# sandwich.net
KiCad netlist of a schematic drawn in EAGLE
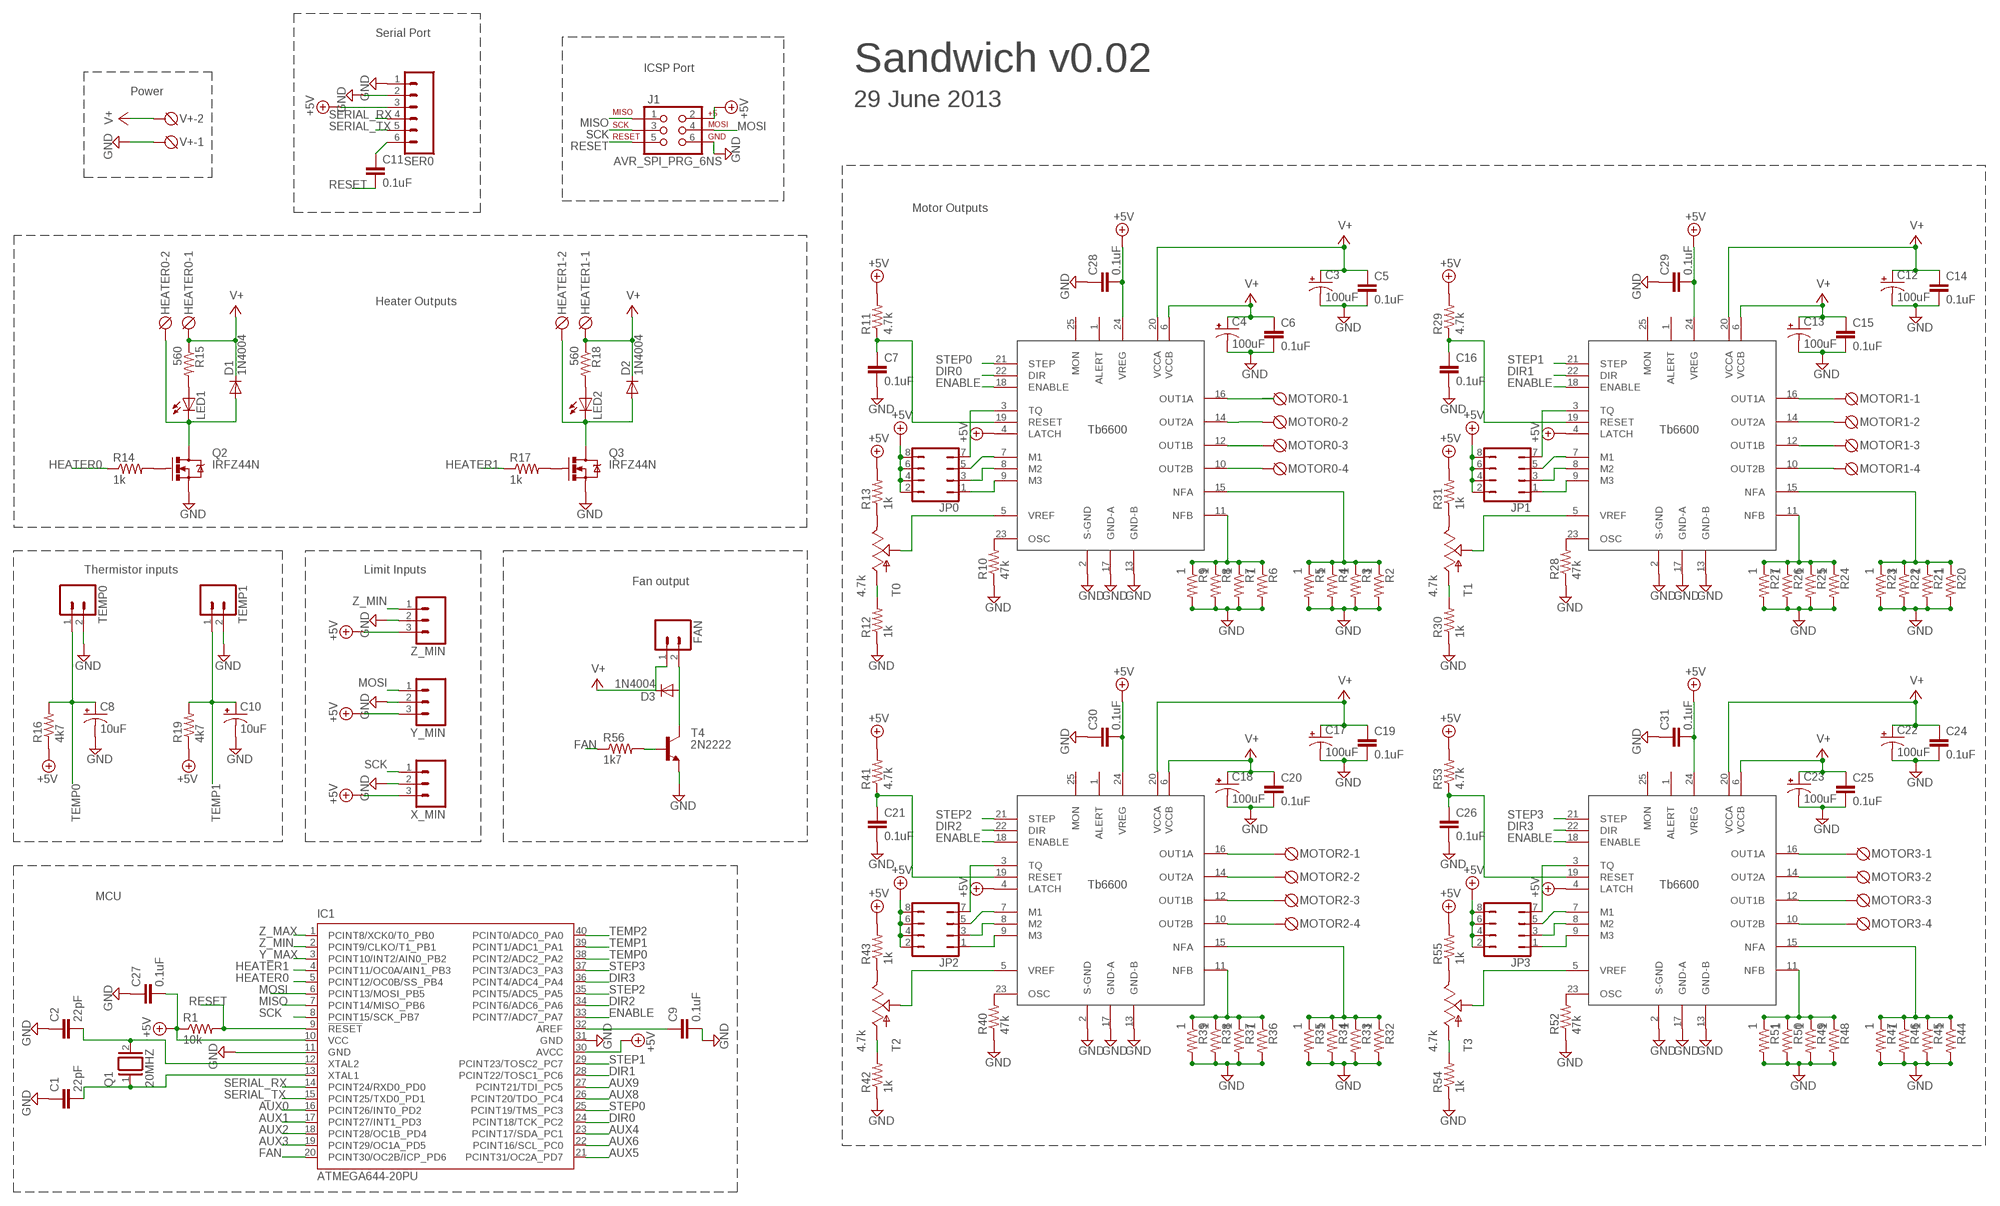
[diagram p0: schematic, sheet 1]

(export (version "E")
  (design (tool "Eeschema 10.0.6"))
  (components
    (comp (ref "C1")
      (value "22pF")
      (footprint "eagle-import:CAP-PTH-SMALL2")
      (libsource (lib "eagle-import") (part "CAPPTH2"))
    )
    (comp (ref "C2")
      (value "22pF")
      (footprint "eagle-import:CAP-PTH-SMALL2")
      (libsource (lib "eagle-import") (part "CAPPTH2"))
    )
    (comp (ref "C3")
      (value "100uF")
      (footprint "eagle-import:CPOL-RADIAL-10UF-25V")
      (libsource (lib "eagle-import") (part "SparkFun-Passives_CAP_POLPTH2"))
    )
    (comp (ref "C4")
      (value "100uF")
      (footprint "eagle-import:CPOL-RADIAL-10UF-25V")
      (libsource (lib "eagle-import") (part "SparkFun-Passives_CAP_POLPTH2"))
    )
    (comp (ref "C5")
      (value "0.1uF")
      (footprint "eagle-import:CAP-PTH-SMALL")
      (libsource (lib "eagle-import") (part "CAPPTH"))
    )
    (comp (ref "C6")
      (value "0.1uF")
      (footprint "eagle-import:CAP-PTH-SMALL")
      (libsource (lib "eagle-import") (part "CAPPTH"))
    )
    (comp (ref "C7")
      (value "0.1uF")
      (footprint "eagle-import:CAP-PTH-SMALL")
      (libsource (lib "eagle-import") (part "CAPPTH"))
    )
    (comp (ref "C8")
      (value "10uF")
      (footprint "eagle-import:CPOL-RADIAL-10UF-25V")
      (libsource (lib "eagle-import") (part "CAP_POLPTH2"))
    )
    (comp (ref "C9")
      (value "0.1uF")
      (footprint "eagle-import:CAP-PTH-SMALL")
      (libsource (lib "eagle-import") (part "CAPPTH"))
    )
    (comp (ref "C10")
      (value "10uF")
      (footprint "eagle-import:CPOL-RADIAL-10UF-25V")
      (libsource (lib "eagle-import") (part "CAP_POLPTH2"))
    )
    (comp (ref "C11")
      (value "0.1uF")
      (footprint "eagle-import:CAP-PTH-SMALL")
      (libsource (lib "eagle-import") (part "SparkFun-Passives_CAPPTH"))
    )
    (comp (ref "C12")
      (value "100uF")
      (footprint "eagle-import:CPOL-RADIAL-10UF-25V")
      (libsource (lib "eagle-import") (part "SparkFun-Passives_CAP_POLPTH2"))
    )
    (comp (ref "C13")
      (value "100uF")
      (footprint "eagle-import:CPOL-RADIAL-10UF-25V")
      (libsource (lib "eagle-import") (part "SparkFun-Passives_CAP_POLPTH2"))
    )
    (comp (ref "C14")
      (value "0.1uF")
      (footprint "eagle-import:CAP-PTH-SMALL")
      (libsource (lib "eagle-import") (part "CAPPTH"))
    )
    (comp (ref "C15")
      (value "0.1uF")
      (footprint "eagle-import:CAP-PTH-SMALL")
      (libsource (lib "eagle-import") (part "CAPPTH"))
    )
    (comp (ref "C16")
      (value "0.1uF")
      (footprint "eagle-import:CAP-PTH-SMALL")
      (libsource (lib "eagle-import") (part "CAPPTH"))
    )
    (comp (ref "C17")
      (value "100uF")
      (footprint "eagle-import:CPOL-RADIAL-10UF-25V")
      (libsource (lib "eagle-import") (part "SparkFun-Passives_CAP_POLPTH2"))
    )
    (comp (ref "C18")
      (value "100uF")
      (footprint "eagle-import:CPOL-RADIAL-10UF-25V")
      (libsource (lib "eagle-import") (part "SparkFun-Passives_CAP_POLPTH2"))
    )
    (comp (ref "C19")
      (value "0.1uF")
      (footprint "eagle-import:CAP-PTH-SMALL")
      (libsource (lib "eagle-import") (part "CAPPTH"))
    )
    (comp (ref "C20")
      (value "0.1uF")
      (footprint "eagle-import:CAP-PTH-SMALL")
      (libsource (lib "eagle-import") (part "CAPPTH"))
    )
    (comp (ref "C21")
      (value "0.1uF")
      (footprint "eagle-import:CAP-PTH-SMALL")
      (libsource (lib "eagle-import") (part "CAPPTH"))
    )
    (comp (ref "C22")
      (value "100uF")
      (footprint "eagle-import:CPOL-RADIAL-10UF-25V")
      (libsource (lib "eagle-import") (part "SparkFun-Passives_CAP_POLPTH2"))
    )
    (comp (ref "C23")
      (value "100uF")
      (footprint "eagle-import:CPOL-RADIAL-10UF-25V")
      (libsource (lib "eagle-import") (part "SparkFun-Passives_CAP_POLPTH2"))
    )
    (comp (ref "C24")
      (value "0.1uF")
      (footprint "eagle-import:CAP-PTH-SMALL")
      (libsource (lib "eagle-import") (part "CAPPTH"))
    )
    (comp (ref "C25")
      (value "0.1uF")
      (footprint "eagle-import:CAP-PTH-SMALL")
      (libsource (lib "eagle-import") (part "CAPPTH"))
    )
    (comp (ref "C26")
      (value "0.1uF")
      (footprint "eagle-import:CAP-PTH-SMALL")
      (libsource (lib "eagle-import") (part "CAPPTH"))
    )
    (comp (ref "C27")
      (value "0.1uF")
      (footprint "eagle-import:CAP-PTH-SMALL")
      (libsource (lib "eagle-import") (part "CAPPTH"))
    )
    (comp (ref "C28")
      (value "0.1uF")
      (footprint "eagle-import:CAP-PTH-SMALL")
      (libsource (lib "eagle-import") (part "CAPPTH"))
    )
    (comp (ref "C29")
      (value "0.1uF")
      (footprint "eagle-import:CAP-PTH-SMALL")
      (libsource (lib "eagle-import") (part "CAPPTH"))
    )
    (comp (ref "C30")
      (value "0.1uF")
      (footprint "eagle-import:CAP-PTH-SMALL")
      (libsource (lib "eagle-import") (part "CAPPTH"))
    )
    (comp (ref "C31")
      (value "0.1uF")
      (footprint "eagle-import:CAP-PTH-SMALL")
      (libsource (lib "eagle-import") (part "CAPPTH"))
    )
    (comp (ref "D1")
      (value "1N4004")
      (footprint "eagle-import:DO41-10")
      (libsource (lib "eagle-import") (part "1N4004"))
    )
    (comp (ref "D2")
      (value "1N4004")
      (footprint "eagle-import:DO41-10")
      (libsource (lib "eagle-import") (part "1N4004"))
    )
    (comp (ref "D3")
      (value "1N4004")
      (footprint "eagle-import:DIODE-1N4001")
      (libsource (lib "eagle-import") (part "DIODEPTH"))
    )
    (comp (ref "FAN")
      (value "M02PTH3")
      (footprint "eagle-import:1X02_LONGPADS")
      (libsource (lib "eagle-import") (part "M02PTH3"))
    )
    (comp (ref "HEATER0")
      (value "DG3XX-02-3.5")
      (footprint "eagle-import:DG350-3.5-02P")
      (libsource (lib "eagle-import") (part "DG3XX-02-3.5"))
    )
    (comp (ref "HEATER1")
      (value "DG3XX-02-3.5")
      (footprint "eagle-import:DG350-3.5-02P")
      (libsource (lib "eagle-import") (part "DG3XX-02-3.5"))
    )
    (comp (ref "IC1")
      (value "ATMEGA644-20PU")
      (footprint "eagle-import:DIL40")
      (libsource (lib "eagle-import") (part "ATMEGA644-PU20"))
    )
    (comp (ref "J1")
      (value "AVR_SPI_PRG_6NS")
      (footprint "eagle-import:2X3-NS")
      (libsource (lib "eagle-import") (part "AVR_SPI_PRG_6NS"))
    )
    (comp (ref "JP0")
      (value "JP4Q")
      (footprint "eagle-import:JP4Q")
      (libsource (lib "eagle-import") (part "JP4Q"))
    )
    (comp (ref "JP1")
      (value "JP4Q")
      (footprint "eagle-import:JP4Q")
      (libsource (lib "eagle-import") (part "JP4Q"))
    )
    (comp (ref "JP2")
      (value "JP4Q")
      (footprint "eagle-import:JP4Q")
      (libsource (lib "eagle-import") (part "JP4Q"))
    )
    (comp (ref "JP3")
      (value "JP4Q")
      (footprint "eagle-import:JP4Q")
      (libsource (lib "eagle-import") (part "JP4Q"))
    )
    (comp (ref "LED1")
      (value "LED5MM")
      (footprint "eagle-import:LED5MM")
      (libsource (lib "eagle-import") (part "LED5MM"))
    )
    (comp (ref "LED2")
      (value "LED5MM")
      (footprint "eagle-import:LED5MM")
      (libsource (lib "eagle-import") (part "LED5MM"))
    )
    (comp (ref "MOTOR0")
      (value "DG3XX-04-3.5")
      (footprint "eagle-import:DG350-3.5-04P")
      (libsource (lib "eagle-import") (part "DG3XX-04-3.5"))
    )
    (comp (ref "MOTOR1")
      (value "DG3XX-04-3.5")
      (footprint "eagle-import:DG350-3.5-04P")
      (libsource (lib "eagle-import") (part "DG3XX-04-3.5"))
    )
    (comp (ref "MOTOR2")
      (value "DG3XX-04-3.5")
      (footprint "eagle-import:DG350-3.5-04P")
      (libsource (lib "eagle-import") (part "DG3XX-04-3.5"))
    )
    (comp (ref "MOTOR3")
      (value "DG3XX-04-3.5")
      (footprint "eagle-import:DG350-3.5-04P")
      (libsource (lib "eagle-import") (part "DG3XX-04-3.5"))
    )
    (comp (ref "Q1")
      (value "20MHZ")
      (footprint "eagle-import:QS")
      (libsource (lib "eagle-import") (part "XTAL/S"))
    )
    (comp (ref "Q2")
      (value "IRFZ44N")
      (footprint "eagle-import:TO220V")
      (libsource (lib "eagle-import") (part "MOSFET-NCHANNELFQP30N06L"))
    )
    (comp (ref "Q3")
      (value "IRFZ44N")
      (footprint "eagle-import:TO220V")
      (libsource (lib "eagle-import") (part "MOSFET-NCHANNELFQP30N06L"))
    )
    (comp (ref "R1")
      (value "10k")
      (footprint "eagle-import:0204V")
      (libsource (lib "eagle-import") (part "R-US_0204/2V"))
    )
    (comp (ref "R2")
      (value "1")
      (footprint "eagle-import:0204V")
      (libsource (lib "eagle-import") (part "R-US_0204/2V"))
    )
    (comp (ref "R3")
      (value "1")
      (footprint "eagle-import:0204V")
      (libsource (lib "eagle-import") (part "R-US_0204/2V"))
    )
    (comp (ref "R4")
      (value "1")
      (footprint "eagle-import:0204V")
      (libsource (lib "eagle-import") (part "R-US_0204/2V"))
    )
    (comp (ref "R5")
      (value "1")
      (footprint "eagle-import:0204V")
      (libsource (lib "eagle-import") (part "R-US_0204/2V"))
    )
    (comp (ref "R6")
      (value "1")
      (footprint "eagle-import:0204V")
      (libsource (lib "eagle-import") (part "R-US_0204/2V"))
    )
    (comp (ref "R7")
      (value "1")
      (footprint "eagle-import:0204V")
      (libsource (lib "eagle-import") (part "R-US_0204/2V"))
    )
    (comp (ref "R8")
      (value "1")
      (footprint "eagle-import:0204V")
      (libsource (lib "eagle-import") (part "R-US_0204/2V"))
    )
    (comp (ref "R9")
      (value "1")
      (footprint "eagle-import:0204V")
      (libsource (lib "eagle-import") (part "R-US_0204/2V"))
    )
    (comp (ref "R10")
      (value "47k")
      (footprint "eagle-import:0204V")
      (libsource (lib "eagle-import") (part "R-US_0204/2V"))
    )
    (comp (ref "R11")
      (value "4.7k")
      (footprint "eagle-import:0204V")
      (libsource (lib "eagle-import") (part "R-US_0204/2V"))
    )
    (comp (ref "R12")
      (value "1k")
      (footprint "eagle-import:0204V")
      (libsource (lib "eagle-import") (part "R-US_0204/2V"))
    )
    (comp (ref "R13")
      (value "1k")
      (footprint "eagle-import:0204V")
      (libsource (lib "eagle-import") (part "R-US_0204/2V"))
    )
    (comp (ref "R14")
      (value "1k")
      (footprint "eagle-import:0204V")
      (libsource (lib "eagle-import") (part "R-US_0204/2V"))
    )
    (comp (ref "R15")
      (value "560")
      (footprint "eagle-import:0204V")
      (libsource (lib "eagle-import") (part "R-US_0204/2V"))
    )
    (comp (ref "R16")
      (value "4k7")
      (footprint "eagle-import:0204V")
      (libsource (lib "eagle-import") (part "R-US_0204/2V"))
    )
    (comp (ref "R17")
      (value "1k")
      (footprint "eagle-import:0204V")
      (libsource (lib "eagle-import") (part "R-US_0204/2V"))
    )
    (comp (ref "R18")
      (value "560")
      (footprint "eagle-import:0204V")
      (libsource (lib "eagle-import") (part "R-US_0204/2V"))
    )
    (comp (ref "R19")
      (value "4k7")
      (footprint "eagle-import:0204V")
      (libsource (lib "eagle-import") (part "R-US_0204/2V"))
    )
    (comp (ref "R20")
      (value "1")
      (footprint "eagle-import:0204V")
      (libsource (lib "eagle-import") (part "R-US_0204/2V"))
    )
    (comp (ref "R21")
      (value "1")
      (footprint "eagle-import:0204V")
      (libsource (lib "eagle-import") (part "R-US_0204/2V"))
    )
    (comp (ref "R22")
      (value "1")
      (footprint "eagle-import:0204V")
      (libsource (lib "eagle-import") (part "R-US_0204/2V"))
    )
    (comp (ref "R23")
      (value "1")
      (footprint "eagle-import:0204V")
      (libsource (lib "eagle-import") (part "R-US_0204/2V"))
    )
    (comp (ref "R24")
      (value "1")
      (footprint "eagle-import:0204V")
      (libsource (lib "eagle-import") (part "R-US_0204/2V"))
    )
    (comp (ref "R25")
      (value "1")
      (footprint "eagle-import:0204V")
      (libsource (lib "eagle-import") (part "R-US_0204/2V"))
    )
    (comp (ref "R26")
      (value "1")
      (footprint "eagle-import:0204V")
      (libsource (lib "eagle-import") (part "R-US_0204/2V"))
    )
    (comp (ref "R27")
      (value "1")
      (footprint "eagle-import:0204V")
      (libsource (lib "eagle-import") (part "R-US_0204/2V"))
    )
    (comp (ref "R28")
      (value "47k")
      (footprint "eagle-import:0204V")
      (libsource (lib "eagle-import") (part "R-US_0204/2V"))
    )
    (comp (ref "R29")
      (value "4.7k")
      (footprint "eagle-import:0204V")
      (libsource (lib "eagle-import") (part "R-US_0204/2V"))
    )
    (comp (ref "R30")
      (value "1k")
      (footprint "eagle-import:0204V")
      (libsource (lib "eagle-import") (part "R-US_0204/2V"))
    )
    (comp (ref "R31")
      (value "1k")
      (footprint "eagle-import:0204V")
      (libsource (lib "eagle-import") (part "R-US_0204/2V"))
    )
    (comp (ref "R32")
      (value "1")
      (footprint "eagle-import:0204V")
      (libsource (lib "eagle-import") (part "R-US_0204/2V"))
    )
    (comp (ref "R33")
      (value "1")
      (footprint "eagle-import:0204V")
      (libsource (lib "eagle-import") (part "R-US_0204/2V"))
    )
    (comp (ref "R34")
      (value "1")
      (footprint "eagle-import:0204V")
      (libsource (lib "eagle-import") (part "R-US_0204/2V"))
    )
    (comp (ref "R35")
      (value "1")
      (footprint "eagle-import:0204V")
      (libsource (lib "eagle-import") (part "R-US_0204/2V"))
    )
    (comp (ref "R36")
      (value "1")
      (footprint "eagle-import:0204V")
      (libsource (lib "eagle-import") (part "R-US_0204/2V"))
    )
    (comp (ref "R37")
      (value "1")
      (footprint "eagle-import:0204V")
      (libsource (lib "eagle-import") (part "R-US_0204/2V"))
    )
    (comp (ref "R38")
      (value "1")
      (footprint "eagle-import:0204V")
      (libsource (lib "eagle-import") (part "R-US_0204/2V"))
    )
    (comp (ref "R39")
      (value "1")
      (footprint "eagle-import:0204V")
      (libsource (lib "eagle-import") (part "R-US_0204/2V"))
    )
    (comp (ref "R40")
      (value "47k")
      (footprint "eagle-import:0204V")
      (libsource (lib "eagle-import") (part "R-US_0204/2V"))
    )
    (comp (ref "R41")
      (value "4.7k")
      (footprint "eagle-import:0204V")
      (libsource (lib "eagle-import") (part "R-US_0204/2V"))
    )
    (comp (ref "R42")
      (value "1k")
      (footprint "eagle-import:0204V")
      (libsource (lib "eagle-import") (part "R-US_0204/2V"))
    )
    (comp (ref "R43")
      (value "1k")
      (footprint "eagle-import:0204V")
      (libsource (lib "eagle-import") (part "R-US_0204/2V"))
    )
    (comp (ref "R44")
      (value "1")
      (footprint "eagle-import:0204V")
      (libsource (lib "eagle-import") (part "R-US_0204/2V"))
    )
    (comp (ref "R45")
      (value "1")
      (footprint "eagle-import:0204V")
      (libsource (lib "eagle-import") (part "R-US_0204/2V"))
    )
    (comp (ref "R46")
      (value "1")
      (footprint "eagle-import:0204V")
      (libsource (lib "eagle-import") (part "R-US_0204/2V"))
    )
    (comp (ref "R47")
      (value "1")
      (footprint "eagle-import:0204V")
      (libsource (lib "eagle-import") (part "R-US_0204/2V"))
    )
    (comp (ref "R48")
      (value "1")
      (footprint "eagle-import:0204V")
      (libsource (lib "eagle-import") (part "R-US_0204/2V"))
    )
    (comp (ref "R49")
      (value "1")
      (footprint "eagle-import:0204V")
      (libsource (lib "eagle-import") (part "R-US_0204/2V"))
    )
    (comp (ref "R50")
      (value "1")
      (footprint "eagle-import:0204V")
      (libsource (lib "eagle-import") (part "R-US_0204/2V"))
    )
    (comp (ref "R51")
      (value "1")
      (footprint "eagle-import:0204V")
      (libsource (lib "eagle-import") (part "R-US_0204/2V"))
    )
    (comp (ref "R52")
      (value "47k")
      (footprint "eagle-import:0204V")
      (libsource (lib "eagle-import") (part "R-US_0204/2V"))
    )
    (comp (ref "R53")
      (value "4.7k")
      (footprint "eagle-import:0204V")
      (libsource (lib "eagle-import") (part "R-US_0204/2V"))
    )
    (comp (ref "R54")
      (value "1k")
      (footprint "eagle-import:0204V")
      (libsource (lib "eagle-import") (part "R-US_0204/2V"))
    )
    (comp (ref "R55")
      (value "1k")
      (footprint "eagle-import:0204V")
      (libsource (lib "eagle-import") (part "R-US_0204/2V"))
    )
    (comp (ref "R56")
      (value "1k7")
      (footprint "eagle-import:0204V")
      (libsource (lib "eagle-import") (part "R-US_0204/2V"))
    )
    (comp (ref "SER0")
      (value "M06SIP")
      (footprint "eagle-import:1X06")
      (libsource (lib "eagle-import") (part "M06SIP"))
    )
    (comp (ref "T0")
      (value "4.7k")
      (footprint "eagle-import:TRIM_POT")
      (libsource (lib "eagle-import") (part "POTTRIM"))
    )
    (comp (ref "T1")
      (value "4.7k")
      (footprint "eagle-import:TRIM_POT")
      (libsource (lib "eagle-import") (part "POTTRIM"))
    )
    (comp (ref "T2")
      (value "4.7k")
      (footprint "eagle-import:TRIM_POT")
      (libsource (lib "eagle-import") (part "POTTRIM"))
    )
    (comp (ref "T3")
      (value "4.7k")
      (footprint "eagle-import:TRIM_POT")
      (libsource (lib "eagle-import") (part "POTTRIM"))
    )
    (comp (ref "T4")
      (value "2N2222")
      (footprint "eagle-import:TO18")
      (libsource (lib "eagle-import") (part "2N2222"))
    )
    (comp (ref "TEMP0")
      (value "M02PTH3")
      (footprint "eagle-import:1X02_LONGPADS")
      (libsource (lib "eagle-import") (part "M02PTH3"))
    )
    (comp (ref "TEMP1")
      (value "M02PTH3")
      (footprint "eagle-import:1X02_LONGPADS")
      (libsource (lib "eagle-import") (part "M02PTH3"))
    )
    (comp (ref "U$1")
      (value "TB6600HG")
      (footprint "eagle-import:P-HZIP25-1.00G")
      (libsource (lib "eagle-import") (part "TB6600HG"))
    )
    (comp (ref "U$2")
      (value "TB6600HG")
      (footprint "eagle-import:P-HZIP25-1.00G")
      (libsource (lib "eagle-import") (part "TB6600HG"))
    )
    (comp (ref "U$3")
      (value "TB6600HG")
      (footprint "eagle-import:P-HZIP25-1.00G")
      (libsource (lib "eagle-import") (part "TB6600HG"))
    )
    (comp (ref "U$4")
      (value "TB6600HG")
      (footprint "eagle-import:P-HZIP25-1.00G")
      (libsource (lib "eagle-import") (part "TB6600HG"))
    )
    (comp (ref "V+")
      (value "DG3XX-02-3.5")
      (footprint "eagle-import:DG350-3.5-02P")
      (libsource (lib "eagle-import") (part "DG3XX-02-3.5"))
    )
    (comp (ref "X_MIN")
      (value "M03LONGPADS")
      (footprint "eagle-import:1X03_LONGPADS")
      (libsource (lib "eagle-import") (part "M03LONGPADS"))
    )
    (comp (ref "Y_MIN")
      (value "M03LONGPADS")
      (footprint "eagle-import:1X03_LONGPADS")
      (libsource (lib "eagle-import") (part "M03LONGPADS"))
    )
    (comp (ref "Z_MIN")
      (value "M03LONGPADS")
      (footprint "eagle-import:1X03_LONGPADS")
      (libsource (lib "eagle-import") (part "M03LONGPADS"))
    )
  )
  (nets
    (net (code "1") (name "+5V") (class "Default")
      (node (ref "C27") (pin "2") (pinfunction "2_2") (pintype "passive"))
      (node (ref "C28") (pin "2") (pinfunction "2_2") (pintype "passive"))
      (node (ref "C29") (pin "2") (pinfunction "2_2") (pintype "passive"))
      (node (ref "C30") (pin "2") (pinfunction "2_2") (pintype "passive"))
      (node (ref "C31") (pin "2") (pinfunction "2_2") (pintype "passive"))
      (node (ref "IC1") (pin "10") (pinfunction "VCC_10") (pintype "power_in"))
      (node (ref "IC1") (pin "30") (pinfunction "AVCC_30") (pintype "power_in"))
      (node (ref "J1") (pin "2") (pinfunction "2_2") (pintype "passive"))
      (node (ref "JP0") (pin "2") (pinfunction "2_2") (pintype "passive"))
      (node (ref "JP0") (pin "4") (pinfunction "4_4") (pintype "passive"))
      (node (ref "JP0") (pin "6") (pinfunction "6_6") (pintype "passive"))
      (node (ref "JP0") (pin "8") (pinfunction "8_8") (pintype "passive"))
      (node (ref "JP1") (pin "2") (pinfunction "2_2") (pintype "passive"))
      (node (ref "JP1") (pin "4") (pinfunction "4_4") (pintype "passive"))
      (node (ref "JP1") (pin "6") (pinfunction "6_6") (pintype "passive"))
      (node (ref "JP1") (pin "8") (pinfunction "8_8") (pintype "passive"))
      (node (ref "JP2") (pin "2") (pinfunction "2_2") (pintype "passive"))
      (node (ref "JP2") (pin "4") (pinfunction "4_4") (pintype "passive"))
      (node (ref "JP2") (pin "6") (pinfunction "6_6") (pintype "passive"))
      (node (ref "JP2") (pin "8") (pinfunction "8_8") (pintype "passive"))
      (node (ref "JP3") (pin "2") (pinfunction "2_2") (pintype "passive"))
      (node (ref "JP3") (pin "4") (pinfunction "4_4") (pintype "passive"))
      (node (ref "JP3") (pin "6") (pinfunction "6_6") (pintype "passive"))
      (node (ref "JP3") (pin "8") (pinfunction "8_8") (pintype "passive"))
      (node (ref "R1") (pin "1") (pinfunction "1_1") (pintype "passive"))
      (node (ref "R11") (pin "2") (pinfunction "2_2") (pintype "passive"))
      (node (ref "R13") (pin "2") (pinfunction "2_2") (pintype "passive"))
      (node (ref "R16") (pin "1") (pinfunction "1_1") (pintype "passive"))
      (node (ref "R19") (pin "1") (pinfunction "1_1") (pintype "passive"))
      (node (ref "R29") (pin "2") (pinfunction "2_2") (pintype "passive"))
      (node (ref "R31") (pin "2") (pinfunction "2_2") (pintype "passive"))
      (node (ref "R41") (pin "2") (pinfunction "2_2") (pintype "passive"))
      (node (ref "R43") (pin "2") (pinfunction "2_2") (pintype "passive"))
      (node (ref "R53") (pin "2") (pinfunction "2_2") (pintype "passive"))
      (node (ref "R55") (pin "2") (pinfunction "2_2") (pintype "passive"))
      (node (ref "SER0") (pin "3") (pinfunction "3_3") (pintype "passive"))
      (node (ref "U$1") (pin "24") (pinfunction "VREG_24") (pintype "output"))
      (node (ref "U$1") (pin "4") (pinfunction "LATCH_4") (pintype "input"))
      (node (ref "U$2") (pin "24") (pinfunction "VREG_24") (pintype "output"))
      (node (ref "U$2") (pin "4") (pinfunction "LATCH_4") (pintype "input"))
      (node (ref "U$3") (pin "24") (pinfunction "VREG_24") (pintype "output"))
      (node (ref "U$3") (pin "4") (pinfunction "LATCH_4") (pintype "input"))
      (node (ref "U$4") (pin "24") (pinfunction "VREG_24") (pintype "output"))
      (node (ref "U$4") (pin "4") (pinfunction "LATCH_4") (pintype "input"))
      (node (ref "X_MIN") (pin "3") (pinfunction "3_3") (pintype "passive"))
      (node (ref "Y_MIN") (pin "3") (pinfunction "3_3") (pintype "passive"))
      (node (ref "Z_MIN") (pin "3") (pinfunction "3_3") (pintype "passive"))
    )
    (net (code "2") (name "/AUX0") (class "Default")
      (node (ref "IC1") (pin "16") (pinfunction "PCINT26/INT0_PD2_16") (pintype "bidirectional"))
    )
    (net (code "3") (name "/AUX1") (class "Default")
      (node (ref "IC1") (pin "17") (pinfunction "PCINT27/INT1_PD3_17") (pintype "bidirectional"))
    )
    (net (code "4") (name "/AUX2") (class "Default")
      (node (ref "IC1") (pin "18") (pinfunction "PCINT28/OC1B_PD4_18") (pintype "bidirectional"))
    )
    (net (code "5") (name "/AUX3") (class "Default")
      (node (ref "IC1") (pin "19") (pinfunction "PCINT29/OC1A_PD5_19") (pintype "bidirectional"))
    )
    (net (code "6") (name "/AUX4") (class "Default")
      (node (ref "IC1") (pin "23") (pinfunction "PCINT17/SDA_PC1_23") (pintype "bidirectional"))
    )
    (net (code "7") (name "/AUX5") (class "Default")
      (node (ref "IC1") (pin "21") (pinfunction "PCINT31/OC2A_PD7_21") (pintype "bidirectional"))
    )
    (net (code "8") (name "/AUX6") (class "Default")
      (node (ref "IC1") (pin "22") (pinfunction "PCINT16/SCL_PC0_22") (pintype "bidirectional"))
    )
    (net (code "9") (name "/AUX8") (class "Default")
      (node (ref "IC1") (pin "26") (pinfunction "PCINT20/TDO_PC4_26") (pintype "bidirectional"))
    )
    (net (code "10") (name "/AUX9") (class "Default")
      (node (ref "IC1") (pin "27") (pinfunction "PCINT21/TDI_PC5_27") (pintype "bidirectional"))
    )
    (net (code "11") (name "/DIR0") (class "Default")
      (node (ref "IC1") (pin "24") (pinfunction "PCINT18/TCK_PC2_24") (pintype "bidirectional"))
      (node (ref "U$1") (pin "22") (pinfunction "DIR_22") (pintype "input"))
    )
    (net (code "12") (name "/DIR1") (class "Default")
      (node (ref "IC1") (pin "28") (pinfunction "PCINT22/TOSC1_PC6_28") (pintype "bidirectional"))
      (node (ref "U$2") (pin "22") (pinfunction "DIR_22") (pintype "input"))
    )
    (net (code "13") (name "/DIR2") (class "Default")
      (node (ref "IC1") (pin "34") (pinfunction "PCINT6/ADC6_PA6_34") (pintype "bidirectional"))
      (node (ref "U$3") (pin "22") (pinfunction "DIR_22") (pintype "input"))
    )
    (net (code "14") (name "/DIR3") (class "Default")
      (node (ref "IC1") (pin "36") (pinfunction "PCINT4/ADC4_PA4_36") (pintype "bidirectional"))
      (node (ref "U$4") (pin "22") (pinfunction "DIR_22") (pintype "input"))
    )
    (net (code "15") (name "/ENABLE") (class "Default")
      (node (ref "IC1") (pin "33") (pinfunction "PCINT7/ADC7_PA7_33") (pintype "bidirectional"))
      (node (ref "U$1") (pin "18") (pinfunction "ENABLE_18") (pintype "input"))
      (node (ref "U$2") (pin "18") (pinfunction "ENABLE_18") (pintype "input"))
      (node (ref "U$3") (pin "18") (pinfunction "ENABLE_18") (pintype "input"))
      (node (ref "U$4") (pin "18") (pinfunction "ENABLE_18") (pintype "input"))
    )
    (net (code "16") (name "/FAN") (class "Default")
      (node (ref "IC1") (pin "20") (pinfunction "PCINT30/OC2B/ICP_PD6_20") (pintype "bidirectional"))
      (node (ref "R56") (pin "1") (pinfunction "1_1") (pintype "passive"))
    )
    (net (code "17") (name "/HEATER0") (class "Default")
      (node (ref "IC1") (pin "5") (pinfunction "PCINT12/OC0B/SS_PB4_5") (pintype "bidirectional"))
      (node (ref "R14") (pin "1") (pinfunction "1_1") (pintype "passive"))
    )
    (net (code "18") (name "/HEATER1") (class "Default")
      (node (ref "IC1") (pin "4") (pinfunction "PCINT11/OC0A/AIN1_PB3_4") (pintype "bidirectional"))
      (node (ref "R17") (pin "1") (pinfunction "1_1") (pintype "passive"))
    )
    (net (code "19") (name "/MISO") (class "Default")
      (node (ref "IC1") (pin "7") (pinfunction "PCINT14/MISO_PB6_7") (pintype "bidirectional"))
      (node (ref "J1") (pin "1") (pinfunction "1_1") (pintype "passive"))
    )
    (net (code "20") (name "/MOSI") (class "Default")
      (node (ref "IC1") (pin "6") (pinfunction "PCINT13/MOSI_PB5_6") (pintype "bidirectional"))
      (node (ref "J1") (pin "4") (pinfunction "4_4") (pintype "passive"))
      (node (ref "Y_MIN") (pin "1") (pinfunction "1_1") (pintype "passive"))
    )
    (net (code "21") (name "/RESET") (class "Default")
      (node (ref "C11") (pin "2") (pinfunction "2_2") (pintype "passive"))
      (node (ref "IC1") (pin "9") (pinfunction "~{RESET}_9") (pintype "input"))
      (node (ref "J1") (pin "5") (pinfunction "5_5") (pintype "passive"))
      (node (ref "R1") (pin "2") (pinfunction "2_2") (pintype "passive"))
    )
    (net (code "22") (name "/SCK") (class "Default")
      (node (ref "IC1") (pin "8") (pinfunction "PCINT15/SCK_PB7_8") (pintype "bidirectional"))
      (node (ref "J1") (pin "3") (pinfunction "3_3") (pintype "passive"))
      (node (ref "X_MIN") (pin "1") (pinfunction "1_1") (pintype "passive"))
    )
    (net (code "23") (name "/SERIAL_RX") (class "Default")
      (node (ref "IC1") (pin "14") (pinfunction "PCINT24/RXD0_PD0_14") (pintype "bidirectional"))
      (node (ref "SER0") (pin "4") (pinfunction "4_4") (pintype "passive"))
    )
    (net (code "24") (name "/SERIAL_TX") (class "Default")
      (node (ref "IC1") (pin "15") (pinfunction "PCINT25/TXD0_PD1_15") (pintype "bidirectional"))
      (node (ref "SER0") (pin "5") (pinfunction "5_5") (pintype "passive"))
    )
    (net (code "25") (name "/STEP0") (class "Default")
      (node (ref "IC1") (pin "25") (pinfunction "PCINT19/TMS_PC3_25") (pintype "bidirectional"))
      (node (ref "U$1") (pin "21") (pinfunction "STEP_21") (pintype "input"))
    )
    (net (code "26") (name "/STEP1") (class "Default")
      (node (ref "IC1") (pin "29") (pinfunction "PCINT23/TOSC2_PC7_29") (pintype "bidirectional"))
      (node (ref "U$2") (pin "21") (pinfunction "STEP_21") (pintype "input"))
    )
    (net (code "27") (name "/STEP2") (class "Default")
      (node (ref "IC1") (pin "35") (pinfunction "PCINT5/ADC5_PA5_35") (pintype "bidirectional"))
      (node (ref "U$3") (pin "21") (pinfunction "STEP_21") (pintype "input"))
    )
    (net (code "28") (name "/STEP3") (class "Default")
      (node (ref "IC1") (pin "37") (pinfunction "PCINT3/ADC3_PA3_37") (pintype "bidirectional"))
      (node (ref "U$4") (pin "21") (pinfunction "STEP_21") (pintype "input"))
    )
    (net (code "29") (name "/TEMP0") (class "Default")
      (node (ref "C8") (pin "1") (pinfunction "+_1") (pintype "passive"))
      (node (ref "IC1") (pin "38") (pinfunction "PCINT2/ADC2_PA2_38") (pintype "bidirectional"))
      (node (ref "R16") (pin "2") (pinfunction "2_2") (pintype "passive"))
      (node (ref "TEMP0") (pin "1") (pinfunction "1_1") (pintype "passive"))
    )
    (net (code "30") (name "/TEMP1") (class "Default")
      (node (ref "C10") (pin "1") (pinfunction "+_1") (pintype "passive"))
      (node (ref "IC1") (pin "39") (pinfunction "PCINT1/ADC1_PA1_39") (pintype "bidirectional"))
      (node (ref "R19") (pin "2") (pinfunction "2_2") (pintype "passive"))
      (node (ref "TEMP1") (pin "1") (pinfunction "1_1") (pintype "passive"))
    )
    (net (code "31") (name "/TEMP2") (class "Default")
      (node (ref "IC1") (pin "40") (pinfunction "PCINT0/ADC0_PA0_40") (pintype "bidirectional"))
    )
    (net (code "32") (name "/Y_MAX") (class "Default")
      (node (ref "IC1") (pin "3") (pinfunction "PCINT10/INT2/AIN0_PB2_3") (pintype "bidirectional"))
    )
    (net (code "33") (name "/Z_MAX") (class "Default")
      (node (ref "IC1") (pin "1") (pinfunction "PCINT8/XCK0/T0_PB0_1") (pintype "bidirectional"))
    )
    (net (code "34") (name "/Z_MIN") (class "Default")
      (node (ref "IC1") (pin "2") (pinfunction "PCINT9/CLKO/T1_PB1_2") (pintype "bidirectional"))
      (node (ref "Z_MIN") (pin "1") (pinfunction "1_1") (pintype "passive"))
    )
    (net (code "35") (name "GND") (class "Default")
      (node (ref "C1") (pin "1") (pinfunction "1_1") (pintype "passive"))
      (node (ref "C10") (pin "2") (pinfunction "-_2") (pintype "passive"))
      (node (ref "C12") (pin "2") (pinfunction "-_2") (pintype "passive"))
      (node (ref "C13") (pin "2") (pinfunction "-_2") (pintype "passive"))
      (node (ref "C14") (pin "2") (pinfunction "2_2") (pintype "passive"))
      (node (ref "C15") (pin "2") (pinfunction "2_2") (pintype "passive"))
      (node (ref "C16") (pin "2") (pinfunction "2_2") (pintype "passive"))
      (node (ref "C17") (pin "2") (pinfunction "-_2") (pintype "passive"))
      (node (ref "C18") (pin "2") (pinfunction "-_2") (pintype "passive"))
      (node (ref "C19") (pin "2") (pinfunction "2_2") (pintype "passive"))
      (node (ref "C2") (pin "1") (pinfunction "1_1") (pintype "passive"))
      (node (ref "C20") (pin "2") (pinfunction "2_2") (pintype "passive"))
      (node (ref "C21") (pin "2") (pinfunction "2_2") (pintype "passive"))
      (node (ref "C22") (pin "2") (pinfunction "-_2") (pintype "passive"))
      (node (ref "C23") (pin "2") (pinfunction "-_2") (pintype "passive"))
      (node (ref "C24") (pin "2") (pinfunction "2_2") (pintype "passive"))
      (node (ref "C25") (pin "2") (pinfunction "2_2") (pintype "passive"))
      (node (ref "C26") (pin "2") (pinfunction "2_2") (pintype "passive"))
      (node (ref "C27") (pin "1") (pinfunction "1_1") (pintype "passive"))
      (node (ref "C28") (pin "1") (pinfunction "1_1") (pintype "passive"))
      (node (ref "C29") (pin "1") (pinfunction "1_1") (pintype "passive"))
      (node (ref "C3") (pin "2") (pinfunction "-_2") (pintype "passive"))
      (node (ref "C30") (pin "1") (pinfunction "1_1") (pintype "passive"))
      (node (ref "C31") (pin "1") (pinfunction "1_1") (pintype "passive"))
      (node (ref "C4") (pin "2") (pinfunction "-_2") (pintype "passive"))
      (node (ref "C5") (pin "2") (pinfunction "2_2") (pintype "passive"))
      (node (ref "C6") (pin "2") (pinfunction "2_2") (pintype "passive"))
      (node (ref "C7") (pin "2") (pinfunction "2_2") (pintype "passive"))
      (node (ref "C8") (pin "2") (pinfunction "-_2") (pintype "passive"))
      (node (ref "C9") (pin "2") (pinfunction "2_2") (pintype "passive"))
      (node (ref "IC1") (pin "11") (pinfunction "GND_11") (pintype "power_in"))
      (node (ref "IC1") (pin "31") (pinfunction "GND_31") (pintype "power_in"))
      (node (ref "J1") (pin "6") (pinfunction "6_6") (pintype "passive"))
      (node (ref "Q2") (pin "3") (pinfunction "S_3") (pintype "passive"))
      (node (ref "Q3") (pin "3") (pinfunction "S_3") (pintype "passive"))
      (node (ref "R10") (pin "1") (pinfunction "1_1") (pintype "passive"))
      (node (ref "R12") (pin "1") (pinfunction "1_1") (pintype "passive"))
      (node (ref "R2") (pin "2") (pinfunction "2_2") (pintype "passive"))
      (node (ref "R20") (pin "2") (pinfunction "2_2") (pintype "passive"))
      (node (ref "R21") (pin "2") (pinfunction "2_2") (pintype "passive"))
      (node (ref "R22") (pin "2") (pinfunction "2_2") (pintype "passive"))
      (node (ref "R23") (pin "2") (pinfunction "2_2") (pintype "passive"))
      (node (ref "R24") (pin "2") (pinfunction "2_2") (pintype "passive"))
      (node (ref "R25") (pin "2") (pinfunction "2_2") (pintype "passive"))
      (node (ref "R26") (pin "2") (pinfunction "2_2") (pintype "passive"))
      (node (ref "R27") (pin "2") (pinfunction "2_2") (pintype "passive"))
      (node (ref "R28") (pin "1") (pinfunction "1_1") (pintype "passive"))
      (node (ref "R3") (pin "2") (pinfunction "2_2") (pintype "passive"))
      (node (ref "R30") (pin "1") (pinfunction "1_1") (pintype "passive"))
      (node (ref "R32") (pin "2") (pinfunction "2_2") (pintype "passive"))
      (node (ref "R33") (pin "2") (pinfunction "2_2") (pintype "passive"))
      (node (ref "R34") (pin "2") (pinfunction "2_2") (pintype "passive"))
      (node (ref "R35") (pin "2") (pinfunction "2_2") (pintype "passive"))
      (node (ref "R36") (pin "2") (pinfunction "2_2") (pintype "passive"))
      (node (ref "R37") (pin "2") (pinfunction "2_2") (pintype "passive"))
      (node (ref "R38") (pin "2") (pinfunction "2_2") (pintype "passive"))
      (node (ref "R39") (pin "2") (pinfunction "2_2") (pintype "passive"))
      (node (ref "R4") (pin "2") (pinfunction "2_2") (pintype "passive"))
      (node (ref "R40") (pin "1") (pinfunction "1_1") (pintype "passive"))
      (node (ref "R42") (pin "1") (pinfunction "1_1") (pintype "passive"))
      (node (ref "R44") (pin "2") (pinfunction "2_2") (pintype "passive"))
      (node (ref "R45") (pin "2") (pinfunction "2_2") (pintype "passive"))
      (node (ref "R46") (pin "2") (pinfunction "2_2") (pintype "passive"))
      (node (ref "R47") (pin "2") (pinfunction "2_2") (pintype "passive"))
      (node (ref "R48") (pin "2") (pinfunction "2_2") (pintype "passive"))
      (node (ref "R49") (pin "2") (pinfunction "2_2") (pintype "passive"))
      (node (ref "R5") (pin "2") (pinfunction "2_2") (pintype "passive"))
      (node (ref "R50") (pin "2") (pinfunction "2_2") (pintype "passive"))
      (node (ref "R51") (pin "2") (pinfunction "2_2") (pintype "passive"))
      (node (ref "R52") (pin "1") (pinfunction "1_1") (pintype "passive"))
      (node (ref "R54") (pin "1") (pinfunction "1_1") (pintype "passive"))
      (node (ref "R6") (pin "2") (pinfunction "2_2") (pintype "passive"))
      (node (ref "R7") (pin "2") (pinfunction "2_2") (pintype "passive"))
      (node (ref "R8") (pin "2") (pinfunction "2_2") (pintype "passive"))
      (node (ref "R9") (pin "2") (pinfunction "2_2") (pintype "passive"))
      (node (ref "SER0") (pin "1") (pinfunction "1_1") (pintype "passive"))
      (node (ref "SER0") (pin "2") (pinfunction "2_2") (pintype "passive"))
      (node (ref "T4") (pin "1") (pinfunction "E_1") (pintype "passive"))
      (node (ref "TEMP0") (pin "2") (pinfunction "2_2") (pintype "passive"))
      (node (ref "TEMP1") (pin "2") (pinfunction "2_2") (pintype "passive"))
      (node (ref "U$1") (pin "13") (pinfunction "GND-B_13") (pintype "power_in"))
      (node (ref "U$1") (pin "17") (pinfunction "GND-A_17") (pintype "output"))
      (node (ref "U$1") (pin "2") (pinfunction "S-GND_2") (pintype "power_in"))
      (node (ref "U$2") (pin "13") (pinfunction "GND-B_13") (pintype "power_in"))
      (node (ref "U$2") (pin "17") (pinfunction "GND-A_17") (pintype "output"))
      (node (ref "U$2") (pin "2") (pinfunction "S-GND_2") (pintype "power_in"))
      (node (ref "U$3") (pin "13") (pinfunction "GND-B_13") (pintype "power_in"))
      (node (ref "U$3") (pin "17") (pinfunction "GND-A_17") (pintype "output"))
      (node (ref "U$3") (pin "2") (pinfunction "S-GND_2") (pintype "power_in"))
      (node (ref "U$4") (pin "13") (pinfunction "GND-B_13") (pintype "power_in"))
      (node (ref "U$4") (pin "17") (pinfunction "GND-A_17") (pintype "output"))
      (node (ref "U$4") (pin "2") (pinfunction "S-GND_2") (pintype "power_in"))
      (node (ref "V+") (pin "1") (pinfunction "KL_1") (pintype "passive"))
      (node (ref "X_MIN") (pin "2") (pinfunction "2_2") (pintype "passive"))
      (node (ref "Y_MIN") (pin "2") (pinfunction "2_2") (pintype "passive"))
      (node (ref "Z_MIN") (pin "2") (pinfunction "2_2") (pintype "passive"))
    )
    (net (code "36") (name "Net-(C11-Pad1)") (class "Default")
      (node (ref "C11") (pin "1") (pinfunction "1_1") (pintype "passive"))
      (node (ref "SER0") (pin "6") (pinfunction "6_6") (pintype "passive"))
    )
    (net (code "37") (name "Net-(HEATER0B-KL)") (class "Default")
      (node (ref "D1") (pin "A") (pinfunction "A_A") (pintype "passive"))
      (node (ref "HEATER0") (pin "2") (pinfunction "KL_2") (pintype "passive"))
      (node (ref "LED1") (pin "K") (pinfunction "C_K") (pintype "passive"))
      (node (ref "Q2") (pin "2") (pinfunction "D_2") (pintype "passive"))
    )
    (net (code "38") (name "Net-(HEATER1B-KL)") (class "Default")
      (node (ref "D2") (pin "A") (pinfunction "A_A") (pintype "passive"))
      (node (ref "HEATER1") (pin "2") (pinfunction "KL_2") (pintype "passive"))
      (node (ref "LED2") (pin "K") (pinfunction "C_K") (pintype "passive"))
      (node (ref "Q3") (pin "2") (pinfunction "D_2") (pintype "passive"))
    )
    (net (code "39") (name "Net-(IC1-AREF)") (class "Default")
      (node (ref "C9") (pin "1") (pinfunction "1_1") (pintype "passive"))
      (node (ref "IC1") (pin "32") (pinfunction "AREF_32") (pintype "passive"))
    )
    (net (code "40") (name "Net-(IC1-XTAL1)") (class "Default")
      (node (ref "C1") (pin "2") (pinfunction "2_2") (pintype "passive"))
      (node (ref "IC1") (pin "13") (pinfunction "XTAL1_13") (pintype "input"))
      (node (ref "Q1") (pin "1") (pinfunction "1_1") (pintype "passive"))
    )
    (net (code "41") (name "Net-(IC1-XTAL2)") (class "Default")
      (node (ref "C2") (pin "2") (pinfunction "2_2") (pintype "passive"))
      (node (ref "IC1") (pin "12") (pinfunction "XTAL2_12") (pintype "output"))
      (node (ref "Q1") (pin "2") (pinfunction "2_2") (pintype "passive"))
    )
    (net (code "42") (name "Net-(LED1-PadA)") (class "Default")
      (node (ref "LED1") (pin "A") (pinfunction "A_A") (pintype "passive"))
      (node (ref "R15") (pin "2") (pinfunction "2_2") (pintype "passive"))
    )
    (net (code "43") (name "Net-(LED2-PadA)") (class "Default")
      (node (ref "LED2") (pin "A") (pinfunction "A_A") (pintype "passive"))
      (node (ref "R18") (pin "2") (pinfunction "2_2") (pintype "passive"))
    )
    (net (code "44") (name "Net-(MOTOR0A-KL)") (class "Default")
      (node (ref "MOTOR0") (pin "1") (pinfunction "KL_1") (pintype "passive"))
      (node (ref "U$1") (pin "16") (pinfunction "OUT1A_16") (pintype "output"))
    )
    (net (code "45") (name "Net-(MOTOR0B-KL)") (class "Default")
      (node (ref "MOTOR0") (pin "2") (pinfunction "KL_2") (pintype "passive"))
      (node (ref "U$1") (pin "14") (pinfunction "OUT2A_14") (pintype "output"))
    )
    (net (code "46") (name "Net-(MOTOR0C-KL)") (class "Default")
      (node (ref "MOTOR0") (pin "3") (pinfunction "KL_3") (pintype "passive"))
      (node (ref "U$1") (pin "12") (pinfunction "OUT1B_12") (pintype "output"))
    )
    (net (code "47") (name "Net-(MOTOR0D-KL)") (class "Default")
      (node (ref "MOTOR0") (pin "4") (pinfunction "KL_4") (pintype "passive"))
      (node (ref "U$1") (pin "10") (pinfunction "OUT2B_10") (pintype "output"))
    )
    (net (code "48") (name "Net-(MOTOR1A-KL)") (class "Default")
      (node (ref "MOTOR1") (pin "1") (pinfunction "KL_1") (pintype "passive"))
      (node (ref "U$2") (pin "16") (pinfunction "OUT1A_16") (pintype "output"))
    )
    (net (code "49") (name "Net-(MOTOR1B-KL)") (class "Default")
      (node (ref "MOTOR1") (pin "2") (pinfunction "KL_2") (pintype "passive"))
      (node (ref "U$2") (pin "14") (pinfunction "OUT2A_14") (pintype "output"))
    )
    (net (code "50") (name "Net-(MOTOR1C-KL)") (class "Default")
      (node (ref "MOTOR1") (pin "3") (pinfunction "KL_3") (pintype "passive"))
      (node (ref "U$2") (pin "12") (pinfunction "OUT1B_12") (pintype "output"))
    )
    (net (code "51") (name "Net-(MOTOR1D-KL)") (class "Default")
      (node (ref "MOTOR1") (pin "4") (pinfunction "KL_4") (pintype "passive"))
      (node (ref "U$2") (pin "10") (pinfunction "OUT2B_10") (pintype "output"))
    )
    (net (code "52") (name "Net-(MOTOR2A-KL)") (class "Default")
      (node (ref "MOTOR2") (pin "1") (pinfunction "KL_1") (pintype "passive"))
      (node (ref "U$3") (pin "16") (pinfunction "OUT1A_16") (pintype "output"))
    )
    (net (code "53") (name "Net-(MOTOR2B-KL)") (class "Default")
      (node (ref "MOTOR2") (pin "2") (pinfunction "KL_2") (pintype "passive"))
      (node (ref "U$3") (pin "14") (pinfunction "OUT2A_14") (pintype "output"))
    )
    (net (code "54") (name "Net-(MOTOR2C-KL)") (class "Default")
      (node (ref "MOTOR2") (pin "3") (pinfunction "KL_3") (pintype "passive"))
      (node (ref "U$3") (pin "12") (pinfunction "OUT1B_12") (pintype "output"))
    )
    (net (code "55") (name "Net-(MOTOR2D-KL)") (class "Default")
      (node (ref "MOTOR2") (pin "4") (pinfunction "KL_4") (pintype "passive"))
      (node (ref "U$3") (pin "10") (pinfunction "OUT2B_10") (pintype "output"))
    )
    (net (code "56") (name "Net-(MOTOR3A-KL)") (class "Default")
      (node (ref "MOTOR3") (pin "1") (pinfunction "KL_1") (pintype "passive"))
      (node (ref "U$4") (pin "16") (pinfunction "OUT1A_16") (pintype "output"))
    )
    (net (code "57") (name "Net-(MOTOR3B-KL)") (class "Default")
      (node (ref "MOTOR3") (pin "2") (pinfunction "KL_2") (pintype "passive"))
      (node (ref "U$4") (pin "14") (pinfunction "OUT2A_14") (pintype "output"))
    )
    (net (code "58") (name "Net-(MOTOR3C-KL)") (class "Default")
      (node (ref "MOTOR3") (pin "3") (pinfunction "KL_3") (pintype "passive"))
      (node (ref "U$4") (pin "12") (pinfunction "OUT1B_12") (pintype "output"))
    )
    (net (code "59") (name "Net-(MOTOR3D-KL)") (class "Default")
      (node (ref "MOTOR3") (pin "4") (pinfunction "KL_4") (pintype "passive"))
      (node (ref "U$4") (pin "10") (pinfunction "OUT2B_10") (pintype "output"))
    )
    (net (code "60") (name "Net-(Q2-G)") (class "Default")
      (node (ref "Q2") (pin "1") (pinfunction "G_1") (pintype "passive"))
      (node (ref "R14") (pin "2") (pinfunction "2_2") (pintype "passive"))
    )
    (net (code "61") (name "Net-(Q3-G)") (class "Default")
      (node (ref "Q3") (pin "1") (pinfunction "G_1") (pintype "passive"))
      (node (ref "R17") (pin "2") (pinfunction "2_2") (pintype "passive"))
    )
    (net (code "62") (name "Net-(T0-A)") (class "Default")
      (node (ref "R12") (pin "2") (pinfunction "2_2") (pintype "passive"))
      (node (ref "T0") (pin "3") (pinfunction "A_3") (pintype "passive"))
    )
    (net (code "63") (name "Net-(T0-E)") (class "Default")
      (node (ref "R13") (pin "1") (pinfunction "1_1") (pintype "passive"))
      (node (ref "T0") (pin "2") (pinfunction "E_2") (pintype "passive"))
    )
    (net (code "64") (name "Net-(T0-S)") (class "Default")
      (node (ref "T0") (pin "1") (pinfunction "S_1") (pintype "passive"))
      (node (ref "U$1") (pin "5") (pinfunction "VREF_5") (pintype "input"))
    )
    (net (code "65") (name "Net-(T1-A)") (class "Default")
      (node (ref "R30") (pin "2") (pinfunction "2_2") (pintype "passive"))
      (node (ref "T1") (pin "3") (pinfunction "A_3") (pintype "passive"))
    )
    (net (code "66") (name "Net-(T1-E)") (class "Default")
      (node (ref "R31") (pin "1") (pinfunction "1_1") (pintype "passive"))
      (node (ref "T1") (pin "2") (pinfunction "E_2") (pintype "passive"))
    )
    (net (code "67") (name "Net-(T1-S)") (class "Default")
      (node (ref "T1") (pin "1") (pinfunction "S_1") (pintype "passive"))
      (node (ref "U$2") (pin "5") (pinfunction "VREF_5") (pintype "input"))
    )
    (net (code "68") (name "Net-(T2-A)") (class "Default")
      (node (ref "R42") (pin "2") (pinfunction "2_2") (pintype "passive"))
      (node (ref "T2") (pin "3") (pinfunction "A_3") (pintype "passive"))
    )
    (net (code "69") (name "Net-(T2-E)") (class "Default")
      (node (ref "R43") (pin "1") (pinfunction "1_1") (pintype "passive"))
      (node (ref "T2") (pin "2") (pinfunction "E_2") (pintype "passive"))
    )
    (net (code "70") (name "Net-(T2-S)") (class "Default")
      (node (ref "T2") (pin "1") (pinfunction "S_1") (pintype "passive"))
      (node (ref "U$3") (pin "5") (pinfunction "VREF_5") (pintype "input"))
    )
    (net (code "71") (name "Net-(T3-A)") (class "Default")
      (node (ref "R54") (pin "2") (pinfunction "2_2") (pintype "passive"))
      (node (ref "T3") (pin "3") (pinfunction "A_3") (pintype "passive"))
    )
    (net (code "72") (name "Net-(T3-E)") (class "Default")
      (node (ref "R55") (pin "1") (pinfunction "1_1") (pintype "passive"))
      (node (ref "T3") (pin "2") (pinfunction "E_2") (pintype "passive"))
    )
    (net (code "73") (name "Net-(T3-S)") (class "Default")
      (node (ref "T3") (pin "1") (pinfunction "S_1") (pintype "passive"))
      (node (ref "U$4") (pin "5") (pinfunction "VREF_5") (pintype "input"))
    )
    (net (code "74") (name "Net-(T4-B)") (class "Default")
      (node (ref "R56") (pin "2") (pinfunction "2_2") (pintype "passive"))
      (node (ref "T4") (pin "2") (pinfunction "B_2") (pintype "passive"))
    )
    (net (code "75") (name "Net-(T4-C)") (class "Default")
      (node (ref "D3") (pin "A") (pinfunction "A_A") (pintype "passive"))
      (node (ref "FAN") (pin "2") (pinfunction "2_2") (pintype "passive"))
      (node (ref "T4") (pin "3") (pinfunction "C_3") (pintype "passive"))
    )
    (net (code "76") (name "Net-(U$1-M1)") (class "Default")
      (node (ref "JP0") (pin "5") (pinfunction "5_5") (pintype "passive"))
      (node (ref "U$1") (pin "7") (pinfunction "M1_7") (pintype "input"))
    )
    (net (code "77") (name "Net-(U$1-M2)") (class "Default")
      (node (ref "JP0") (pin "3") (pinfunction "3_3") (pintype "passive"))
      (node (ref "U$1") (pin "8") (pinfunction "M2_8") (pintype "input"))
    )
    (net (code "78") (name "Net-(U$1-M3)") (class "Default")
      (node (ref "JP0") (pin "1") (pinfunction "1_1") (pintype "passive"))
      (node (ref "U$1") (pin "9") (pinfunction "M3_9") (pintype "input"))
    )
    (net (code "79") (name "Net-(U$1-NFA)") (class "Default")
      (node (ref "R2") (pin "1") (pinfunction "1_1") (pintype "passive"))
      (node (ref "R3") (pin "1") (pinfunction "1_1") (pintype "passive"))
      (node (ref "R4") (pin "1") (pinfunction "1_1") (pintype "passive"))
      (node (ref "R5") (pin "1") (pinfunction "1_1") (pintype "passive"))
      (node (ref "U$1") (pin "15") (pinfunction "NFA_15") (pintype "input"))
    )
    (net (code "80") (name "Net-(U$1-NFB)") (class "Default")
      (node (ref "R6") (pin "1") (pinfunction "1_1") (pintype "passive"))
      (node (ref "R7") (pin "1") (pinfunction "1_1") (pintype "passive"))
      (node (ref "R8") (pin "1") (pinfunction "1_1") (pintype "passive"))
      (node (ref "R9") (pin "1") (pinfunction "1_1") (pintype "passive"))
      (node (ref "U$1") (pin "11") (pinfunction "NFB_11") (pintype "input"))
    )
    (net (code "81") (name "Net-(U$1-OSC)") (class "Default")
      (node (ref "R10") (pin "2") (pinfunction "2_2") (pintype "passive"))
      (node (ref "U$1") (pin "23") (pinfunction "OSC_23") (pintype "input"))
    )
    (net (code "82") (name "Net-(U$1-RESET)") (class "Default")
      (node (ref "C7") (pin "1") (pinfunction "1_1") (pintype "passive"))
      (node (ref "R11") (pin "1") (pinfunction "1_1") (pintype "passive"))
      (node (ref "U$1") (pin "19") (pinfunction "RESET_19") (pintype "input"))
    )
    (net (code "83") (name "Net-(U$1-TQ)") (class "Default")
      (node (ref "JP0") (pin "7") (pinfunction "7_7") (pintype "passive"))
      (node (ref "U$1") (pin "3") (pinfunction "TQ_3") (pintype "input"))
    )
    (net (code "84") (name "Net-(U$2-M1)") (class "Default")
      (node (ref "JP1") (pin "5") (pinfunction "5_5") (pintype "passive"))
      (node (ref "U$2") (pin "7") (pinfunction "M1_7") (pintype "input"))
    )
    (net (code "85") (name "Net-(U$2-M2)") (class "Default")
      (node (ref "JP1") (pin "3") (pinfunction "3_3") (pintype "passive"))
      (node (ref "U$2") (pin "8") (pinfunction "M2_8") (pintype "input"))
    )
    (net (code "86") (name "Net-(U$2-M3)") (class "Default")
      (node (ref "JP1") (pin "1") (pinfunction "1_1") (pintype "passive"))
      (node (ref "U$2") (pin "9") (pinfunction "M3_9") (pintype "input"))
    )
    (net (code "87") (name "Net-(U$2-NFA)") (class "Default")
      (node (ref "R20") (pin "1") (pinfunction "1_1") (pintype "passive"))
      (node (ref "R21") (pin "1") (pinfunction "1_1") (pintype "passive"))
      (node (ref "R22") (pin "1") (pinfunction "1_1") (pintype "passive"))
      (node (ref "R23") (pin "1") (pinfunction "1_1") (pintype "passive"))
      (node (ref "U$2") (pin "15") (pinfunction "NFA_15") (pintype "input"))
    )
    (net (code "88") (name "Net-(U$2-NFB)") (class "Default")
      (node (ref "R24") (pin "1") (pinfunction "1_1") (pintype "passive"))
      (node (ref "R25") (pin "1") (pinfunction "1_1") (pintype "passive"))
      (node (ref "R26") (pin "1") (pinfunction "1_1") (pintype "passive"))
      (node (ref "R27") (pin "1") (pinfunction "1_1") (pintype "passive"))
      (node (ref "U$2") (pin "11") (pinfunction "NFB_11") (pintype "input"))
    )
    (net (code "89") (name "Net-(U$2-OSC)") (class "Default")
      (node (ref "R28") (pin "2") (pinfunction "2_2") (pintype "passive"))
      (node (ref "U$2") (pin "23") (pinfunction "OSC_23") (pintype "input"))
    )
    (net (code "90") (name "Net-(U$2-RESET)") (class "Default")
      (node (ref "C16") (pin "1") (pinfunction "1_1") (pintype "passive"))
      (node (ref "R29") (pin "1") (pinfunction "1_1") (pintype "passive"))
      (node (ref "U$2") (pin "19") (pinfunction "RESET_19") (pintype "input"))
    )
    (net (code "91") (name "Net-(U$2-TQ)") (class "Default")
      (node (ref "JP1") (pin "7") (pinfunction "7_7") (pintype "passive"))
      (node (ref "U$2") (pin "3") (pinfunction "TQ_3") (pintype "input"))
    )
    (net (code "92") (name "Net-(U$3-M1)") (class "Default")
      (node (ref "JP2") (pin "5") (pinfunction "5_5") (pintype "passive"))
      (node (ref "U$3") (pin "7") (pinfunction "M1_7") (pintype "input"))
    )
    (net (code "93") (name "Net-(U$3-M2)") (class "Default")
      (node (ref "JP2") (pin "3") (pinfunction "3_3") (pintype "passive"))
      (node (ref "U$3") (pin "8") (pinfunction "M2_8") (pintype "input"))
    )
    (net (code "94") (name "Net-(U$3-M3)") (class "Default")
      (node (ref "JP2") (pin "1") (pinfunction "1_1") (pintype "passive"))
      (node (ref "U$3") (pin "9") (pinfunction "M3_9") (pintype "input"))
    )
    (net (code "95") (name "Net-(U$3-NFA)") (class "Default")
      (node (ref "R32") (pin "1") (pinfunction "1_1") (pintype "passive"))
      (node (ref "R33") (pin "1") (pinfunction "1_1") (pintype "passive"))
      (node (ref "R34") (pin "1") (pinfunction "1_1") (pintype "passive"))
      (node (ref "R35") (pin "1") (pinfunction "1_1") (pintype "passive"))
      (node (ref "U$3") (pin "15") (pinfunction "NFA_15") (pintype "input"))
    )
    (net (code "96") (name "Net-(U$3-NFB)") (class "Default")
      (node (ref "R36") (pin "1") (pinfunction "1_1") (pintype "passive"))
      (node (ref "R37") (pin "1") (pinfunction "1_1") (pintype "passive"))
      (node (ref "R38") (pin "1") (pinfunction "1_1") (pintype "passive"))
      (node (ref "R39") (pin "1") (pinfunction "1_1") (pintype "passive"))
      (node (ref "U$3") (pin "11") (pinfunction "NFB_11") (pintype "input"))
    )
    (net (code "97") (name "Net-(U$3-OSC)") (class "Default")
      (node (ref "R40") (pin "2") (pinfunction "2_2") (pintype "passive"))
      (node (ref "U$3") (pin "23") (pinfunction "OSC_23") (pintype "input"))
    )
    (net (code "98") (name "Net-(U$3-RESET)") (class "Default")
      (node (ref "C21") (pin "1") (pinfunction "1_1") (pintype "passive"))
      (node (ref "R41") (pin "1") (pinfunction "1_1") (pintype "passive"))
      (node (ref "U$3") (pin "19") (pinfunction "RESET_19") (pintype "input"))
    )
    (net (code "99") (name "Net-(U$3-TQ)") (class "Default")
      (node (ref "JP2") (pin "7") (pinfunction "7_7") (pintype "passive"))
      (node (ref "U$3") (pin "3") (pinfunction "TQ_3") (pintype "input"))
    )
    (net (code "100") (name "Net-(U$4-M1)") (class "Default")
      (node (ref "JP3") (pin "5") (pinfunction "5_5") (pintype "passive"))
      (node (ref "U$4") (pin "7") (pinfunction "M1_7") (pintype "input"))
    )
    (net (code "101") (name "Net-(U$4-M2)") (class "Default")
      (node (ref "JP3") (pin "3") (pinfunction "3_3") (pintype "passive"))
      (node (ref "U$4") (pin "8") (pinfunction "M2_8") (pintype "input"))
    )
    (net (code "102") (name "Net-(U$4-M3)") (class "Default")
      (node (ref "JP3") (pin "1") (pinfunction "1_1") (pintype "passive"))
      (node (ref "U$4") (pin "9") (pinfunction "M3_9") (pintype "input"))
    )
    (net (code "103") (name "Net-(U$4-NFA)") (class "Default")
      (node (ref "R44") (pin "1") (pinfunction "1_1") (pintype "passive"))
      (node (ref "R45") (pin "1") (pinfunction "1_1") (pintype "passive"))
      (node (ref "R46") (pin "1") (pinfunction "1_1") (pintype "passive"))
      (node (ref "R47") (pin "1") (pinfunction "1_1") (pintype "passive"))
      (node (ref "U$4") (pin "15") (pinfunction "NFA_15") (pintype "input"))
    )
    (net (code "104") (name "Net-(U$4-NFB)") (class "Default")
      (node (ref "R48") (pin "1") (pinfunction "1_1") (pintype "passive"))
      (node (ref "R49") (pin "1") (pinfunction "1_1") (pintype "passive"))
      (node (ref "R50") (pin "1") (pinfunction "1_1") (pintype "passive"))
      (node (ref "R51") (pin "1") (pinfunction "1_1") (pintype "passive"))
      (node (ref "U$4") (pin "11") (pinfunction "NFB_11") (pintype "input"))
    )
    (net (code "105") (name "Net-(U$4-OSC)") (class "Default")
      (node (ref "R52") (pin "2") (pinfunction "2_2") (pintype "passive"))
      (node (ref "U$4") (pin "23") (pinfunction "OSC_23") (pintype "input"))
    )
    (net (code "106") (name "Net-(U$4-RESET)") (class "Default")
      (node (ref "C26") (pin "1") (pinfunction "1_1") (pintype "passive"))
      (node (ref "R53") (pin "1") (pinfunction "1_1") (pintype "passive"))
      (node (ref "U$4") (pin "19") (pinfunction "RESET_19") (pintype "input"))
    )
    (net (code "107") (name "Net-(U$4-TQ)") (class "Default")
      (node (ref "JP3") (pin "7") (pinfunction "7_7") (pintype "passive"))
      (node (ref "U$4") (pin "3") (pinfunction "TQ_3") (pintype "input"))
    )
    (net (code "108") (name "V+") (class "Default")
      (node (ref "C12") (pin "1") (pinfunction "+_1") (pintype "passive"))
      (node (ref "C13") (pin "1") (pinfunction "+_1") (pintype "passive"))
      (node (ref "C14") (pin "1") (pinfunction "1_1") (pintype "passive"))
      (node (ref "C15") (pin "1") (pinfunction "1_1") (pintype "passive"))
      (node (ref "C17") (pin "1") (pinfunction "+_1") (pintype "passive"))
      (node (ref "C18") (pin "1") (pinfunction "+_1") (pintype "passive"))
      (node (ref "C19") (pin "1") (pinfunction "1_1") (pintype "passive"))
      (node (ref "C20") (pin "1") (pinfunction "1_1") (pintype "passive"))
      (node (ref "C22") (pin "1") (pinfunction "+_1") (pintype "passive"))
      (node (ref "C23") (pin "1") (pinfunction "+_1") (pintype "passive"))
      (node (ref "C24") (pin "1") (pinfunction "1_1") (pintype "passive"))
      (node (ref "C25") (pin "1") (pinfunction "1_1") (pintype "passive"))
      (node (ref "C3") (pin "1") (pinfunction "+_1") (pintype "passive"))
      (node (ref "C4") (pin "1") (pinfunction "+_1") (pintype "passive"))
      (node (ref "C5") (pin "1") (pinfunction "1_1") (pintype "passive"))
      (node (ref "C6") (pin "1") (pinfunction "1_1") (pintype "passive"))
      (node (ref "D1") (pin "C") (pinfunction "C_C") (pintype "passive"))
      (node (ref "D2") (pin "C") (pinfunction "C_C") (pintype "passive"))
      (node (ref "D3") (pin "C") (pinfunction "C_C") (pintype "passive"))
      (node (ref "FAN") (pin "1") (pinfunction "1_1") (pintype "passive"))
      (node (ref "HEATER0") (pin "1") (pinfunction "KL_1") (pintype "passive"))
      (node (ref "HEATER1") (pin "1") (pinfunction "KL_1") (pintype "passive"))
      (node (ref "R15") (pin "1") (pinfunction "1_1") (pintype "passive"))
      (node (ref "R18") (pin "1") (pinfunction "1_1") (pintype "passive"))
      (node (ref "U$1") (pin "20") (pinfunction "VCCA_20") (pintype "power_in"))
      (node (ref "U$1") (pin "6") (pinfunction "VCCB_6") (pintype "power_in"))
      (node (ref "U$2") (pin "20") (pinfunction "VCCA_20") (pintype "power_in"))
      (node (ref "U$2") (pin "6") (pinfunction "VCCB_6") (pintype "power_in"))
      (node (ref "U$3") (pin "20") (pinfunction "VCCA_20") (pintype "power_in"))
      (node (ref "U$3") (pin "6") (pinfunction "VCCB_6") (pintype "power_in"))
      (node (ref "U$4") (pin "20") (pinfunction "VCCA_20") (pintype "power_in"))
      (node (ref "U$4") (pin "6") (pinfunction "VCCB_6") (pintype "power_in"))
      (node (ref "V+") (pin "2") (pinfunction "KL_2") (pintype "passive"))
    )
    (net (code "109") (name "unconnected-(U$1-ALERT-Pad1)") (class "Default")
      (node (ref "U$1") (pin "1") (pinfunction "ALERT_1") (pintype "output"))
    )
    (net (code "110") (name "unconnected-(U$1-MON-Pad25)") (class "Default")
      (node (ref "U$1") (pin "25") (pinfunction "MON_25") (pintype "output"))
    )
    (net (code "111") (name "unconnected-(U$2-ALERT-Pad1)") (class "Default")
      (node (ref "U$2") (pin "1") (pinfunction "ALERT_1") (pintype "output"))
    )
    (net (code "112") (name "unconnected-(U$2-MON-Pad25)") (class "Default")
      (node (ref "U$2") (pin "25") (pinfunction "MON_25") (pintype "output"))
    )
    (net (code "113") (name "unconnected-(U$3-ALERT-Pad1)") (class "Default")
      (node (ref "U$3") (pin "1") (pinfunction "ALERT_1") (pintype "output"))
    )
    (net (code "114") (name "unconnected-(U$3-MON-Pad25)") (class "Default")
      (node (ref "U$3") (pin "25") (pinfunction "MON_25") (pintype "output"))
    )
    (net (code "115") (name "unconnected-(U$4-ALERT-Pad1)") (class "Default")
      (node (ref "U$4") (pin "1") (pinfunction "ALERT_1") (pintype "output"))
    )
    (net (code "116") (name "unconnected-(U$4-MON-Pad25)") (class "Default")
      (node (ref "U$4") (pin "25") (pinfunction "MON_25") (pintype "output"))
    )
  )
)
